# 4-layer-microstrip-osh.net
KiCad netlist of a schematic drawn in EAGLE
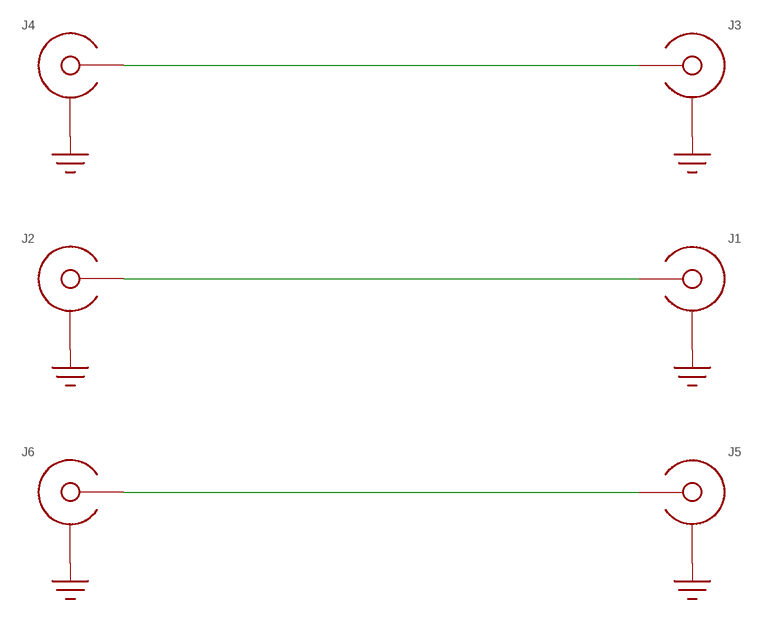
[diagram p0: schematic, sheet 1]

(export (version "E")
  (design (tool "Eeschema 10.0.6"))
  (components
    (comp (ref "J1")
      (value "SMA-EDGE-LAUNCH4L_4045_TAPER")
      (footprint "eagle-import:SMA_EDGE_LAUNCH_4L_4045_TAPER")
      (libsource (lib "eagle-import") (part "SMA-EDGE-LAUNCH4L_4045_TAPER"))
    )
    (comp (ref "J2")
      (value "SMA-EDGE-LAUNCH4L_4040_TAPER")
      (footprint "eagle-import:SMA_EDGE_LAUNCH_4L_4040_TAPER")
      (libsource (lib "eagle-import") (part "SMA-EDGE-LAUNCH4L_4040_TAPER"))
    )
    (comp (ref "J3")
      (value "SMA-EDGE-LAUNCH4L_4035_TAPER")
      (footprint "eagle-import:SMA_EDGE_LAUNCH_4L_4035_TAPER")
      (libsource (lib "eagle-import") (part "SMA-EDGE-LAUNCH4L_4035_TAPER"))
    )
    (comp (ref "J4")
      (value "SMA-EDGE-LAUNCH4L_4020_TAPER")
      (footprint "eagle-import:SMA_EDGE_LAUNCH_4L_4020_TAPER")
      (libsource (lib "eagle-import") (part "SMA-EDGE-LAUNCH4L_4020_TAPER"))
    )
    (comp (ref "J5")
      (value "SMA-EDGE-LAUNCH4L_4030_TAPER")
      (footprint "eagle-import:SMA_EDGE_LAUNCH_4L_4030_TAPER")
      (libsource (lib "eagle-import") (part "SMA-EDGE-LAUNCH4L_4030_TAPER"))
    )
    (comp (ref "J6")
      (value "SMA-EDGE-LAUNCH4L_4025_TAPER")
      (footprint "eagle-import:SMA_EDGE_LAUNCH_4L_4025_TAPER")
      (libsource (lib "eagle-import") (part "SMA-EDGE-LAUNCH4L_4025_TAPER"))
    )
  )
  (nets
    (net (code "1") (name "GND") (class "Default")
      (node (ref "J1") (pin "BOTTOM_GND") (pinfunction "SHIELD_BOTTOM_GND") (pintype "bidirectional"))
      (node (ref "J1") (pin "GND@1") (pinfunction "SHIELD_GND@1") (pintype "bidirectional"))
      (node (ref "J1") (pin "GND@14") (pinfunction "SHIELD_GND@14") (pintype "bidirectional"))
      (node (ref "J1") (pin "GND@15") (pinfunction "SHIELD_GND@15") (pintype "bidirectional"))
      (node (ref "J1") (pin "GND@16") (pinfunction "SHIELD_GND@16") (pintype "bidirectional"))
      (node (ref "J1") (pin "GND@17") (pinfunction "SHIELD_GND@17") (pintype "bidirectional"))
      (node (ref "J1") (pin "GND@2") (pinfunction "SHIELD_GND@2") (pintype "bidirectional"))
      (node (ref "J1") (pin "GND@3") (pinfunction "SHIELD_GND@3") (pintype "bidirectional"))
      (node (ref "J1") (pin "GND@4") (pinfunction "SHIELD_GND@4") (pintype "bidirectional"))
      (node (ref "J1") (pin "GND@5") (pinfunction "SHIELD_GND@5") (pintype "bidirectional"))
      (node (ref "J1") (pin "GND@6") (pinfunction "SHIELD_GND@6") (pintype "bidirectional"))
      (node (ref "J1") (pin "GND@7") (pinfunction "SHIELD_GND@7") (pintype "bidirectional"))
      (node (ref "J1") (pin "GND@8") (pinfunction "SHIELD_GND@8") (pintype "bidirectional"))
      (node (ref "J1") (pin "GND_PAD1") (pinfunction "SHIELD_GND_PAD1") (pintype "bidirectional"))
      (node (ref "J1") (pin "GND_PAD2") (pinfunction "SHIELD_GND_PAD2") (pintype "bidirectional"))
      (node (ref "J1") (pin "P$1") (pinfunction "SHIELD_P$1") (pintype "bidirectional"))
      (node (ref "J1") (pin "P$2") (pinfunction "SHIELD_P$2") (pintype "bidirectional"))
      (node (ref "J2") (pin "BOTTOM_GND") (pinfunction "SHIELD_BOTTOM_GND") (pintype "bidirectional"))
      (node (ref "J2") (pin "GND@1") (pinfunction "SHIELD_GND@1") (pintype "bidirectional"))
      (node (ref "J2") (pin "GND@14") (pinfunction "SHIELD_GND@14") (pintype "bidirectional"))
      (node (ref "J2") (pin "GND@15") (pinfunction "SHIELD_GND@15") (pintype "bidirectional"))
      (node (ref "J2") (pin "GND@16") (pinfunction "SHIELD_GND@16") (pintype "bidirectional"))
      (node (ref "J2") (pin "GND@17") (pinfunction "SHIELD_GND@17") (pintype "bidirectional"))
      (node (ref "J2") (pin "GND@2") (pinfunction "SHIELD_GND@2") (pintype "bidirectional"))
      (node (ref "J2") (pin "GND@3") (pinfunction "SHIELD_GND@3") (pintype "bidirectional"))
      (node (ref "J2") (pin "GND@4") (pinfunction "SHIELD_GND@4") (pintype "bidirectional"))
      (node (ref "J2") (pin "GND@5") (pinfunction "SHIELD_GND@5") (pintype "bidirectional"))
      (node (ref "J2") (pin "GND@6") (pinfunction "SHIELD_GND@6") (pintype "bidirectional"))
      (node (ref "J2") (pin "GND@7") (pinfunction "SHIELD_GND@7") (pintype "bidirectional"))
      (node (ref "J2") (pin "GND@8") (pinfunction "SHIELD_GND@8") (pintype "bidirectional"))
      (node (ref "J2") (pin "GND_PAD1") (pinfunction "SHIELD_GND_PAD1") (pintype "bidirectional"))
      (node (ref "J2") (pin "GND_PAD2") (pinfunction "SHIELD_GND_PAD2") (pintype "bidirectional"))
      (node (ref "J2") (pin "P$1") (pinfunction "SHIELD_P$1") (pintype "bidirectional"))
      (node (ref "J2") (pin "P$2") (pinfunction "SHIELD_P$2") (pintype "bidirectional"))
      (node (ref "J3") (pin "BOTTOM_GND") (pinfunction "SHIELD_BOTTOM_GND") (pintype "bidirectional"))
      (node (ref "J3") (pin "GND@1") (pinfunction "SHIELD_GND@1") (pintype "bidirectional"))
      (node (ref "J3") (pin "GND@14") (pinfunction "SHIELD_GND@14") (pintype "bidirectional"))
      (node (ref "J3") (pin "GND@15") (pinfunction "SHIELD_GND@15") (pintype "bidirectional"))
      (node (ref "J3") (pin "GND@16") (pinfunction "SHIELD_GND@16") (pintype "bidirectional"))
      (node (ref "J3") (pin "GND@17") (pinfunction "SHIELD_GND@17") (pintype "bidirectional"))
      (node (ref "J3") (pin "GND@2") (pinfunction "SHIELD_GND@2") (pintype "bidirectional"))
      (node (ref "J3") (pin "GND@3") (pinfunction "SHIELD_GND@3") (pintype "bidirectional"))
      (node (ref "J3") (pin "GND@4") (pinfunction "SHIELD_GND@4") (pintype "bidirectional"))
      (node (ref "J3") (pin "GND@5") (pinfunction "SHIELD_GND@5") (pintype "bidirectional"))
      (node (ref "J3") (pin "GND@6") (pinfunction "SHIELD_GND@6") (pintype "bidirectional"))
      (node (ref "J3") (pin "GND@7") (pinfunction "SHIELD_GND@7") (pintype "bidirectional"))
      (node (ref "J3") (pin "GND@8") (pinfunction "SHIELD_GND@8") (pintype "bidirectional"))
      (node (ref "J3") (pin "GND_PAD1") (pinfunction "SHIELD_GND_PAD1") (pintype "bidirectional"))
      (node (ref "J3") (pin "GND_PAD2") (pinfunction "SHIELD_GND_PAD2") (pintype "bidirectional"))
      (node (ref "J3") (pin "P$1") (pinfunction "SHIELD_P$1") (pintype "bidirectional"))
      (node (ref "J3") (pin "P$2") (pinfunction "SHIELD_P$2") (pintype "bidirectional"))
      (node (ref "J4") (pin "BOTTOM_GND") (pinfunction "SHIELD_BOTTOM_GND") (pintype "bidirectional"))
      (node (ref "J4") (pin "GND@1") (pinfunction "SHIELD_GND@1") (pintype "bidirectional"))
      (node (ref "J4") (pin "GND@14") (pinfunction "SHIELD_GND@14") (pintype "bidirectional"))
      (node (ref "J4") (pin "GND@15") (pinfunction "SHIELD_GND@15") (pintype "bidirectional"))
      (node (ref "J4") (pin "GND@16") (pinfunction "SHIELD_GND@16") (pintype "bidirectional"))
      (node (ref "J4") (pin "GND@17") (pinfunction "SHIELD_GND@17") (pintype "bidirectional"))
      (node (ref "J4") (pin "GND@2") (pinfunction "SHIELD_GND@2") (pintype "bidirectional"))
      (node (ref "J4") (pin "GND@3") (pinfunction "SHIELD_GND@3") (pintype "bidirectional"))
      (node (ref "J4") (pin "GND@4") (pinfunction "SHIELD_GND@4") (pintype "bidirectional"))
      (node (ref "J4") (pin "GND@5") (pinfunction "SHIELD_GND@5") (pintype "bidirectional"))
      (node (ref "J4") (pin "GND@6") (pinfunction "SHIELD_GND@6") (pintype "bidirectional"))
      (node (ref "J4") (pin "GND@7") (pinfunction "SHIELD_GND@7") (pintype "bidirectional"))
      (node (ref "J4") (pin "GND@8") (pinfunction "SHIELD_GND@8") (pintype "bidirectional"))
      (node (ref "J4") (pin "GND_PAD1") (pinfunction "SHIELD_GND_PAD1") (pintype "bidirectional"))
      (node (ref "J4") (pin "GND_PAD2") (pinfunction "SHIELD_GND_PAD2") (pintype "bidirectional"))
      (node (ref "J4") (pin "P$1") (pinfunction "SHIELD_P$1") (pintype "bidirectional"))
      (node (ref "J4") (pin "P$2") (pinfunction "SHIELD_P$2") (pintype "bidirectional"))
      (node (ref "J5") (pin "BOTTOM_GND") (pinfunction "SHIELD_BOTTOM_GND") (pintype "bidirectional"))
      (node (ref "J5") (pin "GND@1") (pinfunction "SHIELD_GND@1") (pintype "bidirectional"))
      (node (ref "J5") (pin "GND@14") (pinfunction "SHIELD_GND@14") (pintype "bidirectional"))
      (node (ref "J5") (pin "GND@15") (pinfunction "SHIELD_GND@15") (pintype "bidirectional"))
      (node (ref "J5") (pin "GND@16") (pinfunction "SHIELD_GND@16") (pintype "bidirectional"))
      (node (ref "J5") (pin "GND@17") (pinfunction "SHIELD_GND@17") (pintype "bidirectional"))
      (node (ref "J5") (pin "GND@2") (pinfunction "SHIELD_GND@2") (pintype "bidirectional"))
      (node (ref "J5") (pin "GND@3") (pinfunction "SHIELD_GND@3") (pintype "bidirectional"))
      (node (ref "J5") (pin "GND@4") (pinfunction "SHIELD_GND@4") (pintype "bidirectional"))
      (node (ref "J5") (pin "GND@5") (pinfunction "SHIELD_GND@5") (pintype "bidirectional"))
      (node (ref "J5") (pin "GND@6") (pinfunction "SHIELD_GND@6") (pintype "bidirectional"))
      (node (ref "J5") (pin "GND@7") (pinfunction "SHIELD_GND@7") (pintype "bidirectional"))
      (node (ref "J5") (pin "GND@8") (pinfunction "SHIELD_GND@8") (pintype "bidirectional"))
      (node (ref "J5") (pin "GND_PAD1") (pinfunction "SHIELD_GND_PAD1") (pintype "bidirectional"))
      (node (ref "J5") (pin "GND_PAD2") (pinfunction "SHIELD_GND_PAD2") (pintype "bidirectional"))
      (node (ref "J5") (pin "P$1") (pinfunction "SHIELD_P$1") (pintype "bidirectional"))
      (node (ref "J5") (pin "P$2") (pinfunction "SHIELD_P$2") (pintype "bidirectional"))
      (node (ref "J6") (pin "BOTTOM_GND") (pinfunction "SHIELD_BOTTOM_GND") (pintype "bidirectional"))
      (node (ref "J6") (pin "GND@1") (pinfunction "SHIELD_GND@1") (pintype "bidirectional"))
      (node (ref "J6") (pin "GND@14") (pinfunction "SHIELD_GND@14") (pintype "bidirectional"))
      (node (ref "J6") (pin "GND@15") (pinfunction "SHIELD_GND@15") (pintype "bidirectional"))
      (node (ref "J6") (pin "GND@16") (pinfunction "SHIELD_GND@16") (pintype "bidirectional"))
      (node (ref "J6") (pin "GND@17") (pinfunction "SHIELD_GND@17") (pintype "bidirectional"))
      (node (ref "J6") (pin "GND@2") (pinfunction "SHIELD_GND@2") (pintype "bidirectional"))
      (node (ref "J6") (pin "GND@3") (pinfunction "SHIELD_GND@3") (pintype "bidirectional"))
      (node (ref "J6") (pin "GND@4") (pinfunction "SHIELD_GND@4") (pintype "bidirectional"))
      (node (ref "J6") (pin "GND@5") (pinfunction "SHIELD_GND@5") (pintype "bidirectional"))
      (node (ref "J6") (pin "GND@6") (pinfunction "SHIELD_GND@6") (pintype "bidirectional"))
      (node (ref "J6") (pin "GND@7") (pinfunction "SHIELD_GND@7") (pintype "bidirectional"))
      (node (ref "J6") (pin "GND@8") (pinfunction "SHIELD_GND@8") (pintype "bidirectional"))
      (node (ref "J6") (pin "GND_PAD1") (pinfunction "SHIELD_GND_PAD1") (pintype "bidirectional"))
      (node (ref "J6") (pin "GND_PAD2") (pinfunction "SHIELD_GND_PAD2") (pintype "bidirectional"))
      (node (ref "J6") (pin "P$1") (pinfunction "SHIELD_P$1") (pintype "bidirectional"))
      (node (ref "J6") (pin "P$2") (pinfunction "SHIELD_P$2") (pintype "bidirectional"))
    )
    (net (code "2") (name "Net-(J1-CENTER)") (class "Default")
      (node (ref "J1") (pin "CENTER@1") (pinfunction "CENTER_CENTER@1") (pintype "bidirectional"))
      (node (ref "J2") (pin "CENTER@1") (pinfunction "CENTER_CENTER@1") (pintype "bidirectional"))
    )
    (net (code "3") (name "Net-(J3-CENTER)") (class "Default")
      (node (ref "J3") (pin "CENTER@1") (pinfunction "CENTER_CENTER@1") (pintype "bidirectional"))
      (node (ref "J4") (pin "CENTER@1") (pinfunction "CENTER_CENTER@1") (pintype "bidirectional"))
    )
    (net (code "4") (name "Net-(J5-CENTER)") (class "Default")
      (node (ref "J5") (pin "CENTER@1") (pinfunction "CENTER_CENTER@1") (pintype "bidirectional"))
      (node (ref "J6") (pin "CENTER@1") (pinfunction "CENTER_CENTER@1") (pintype "bidirectional"))
    )
  )
)
